# servo_controller_1_2.net
KiCad netlist of a schematic drawn in EAGLE
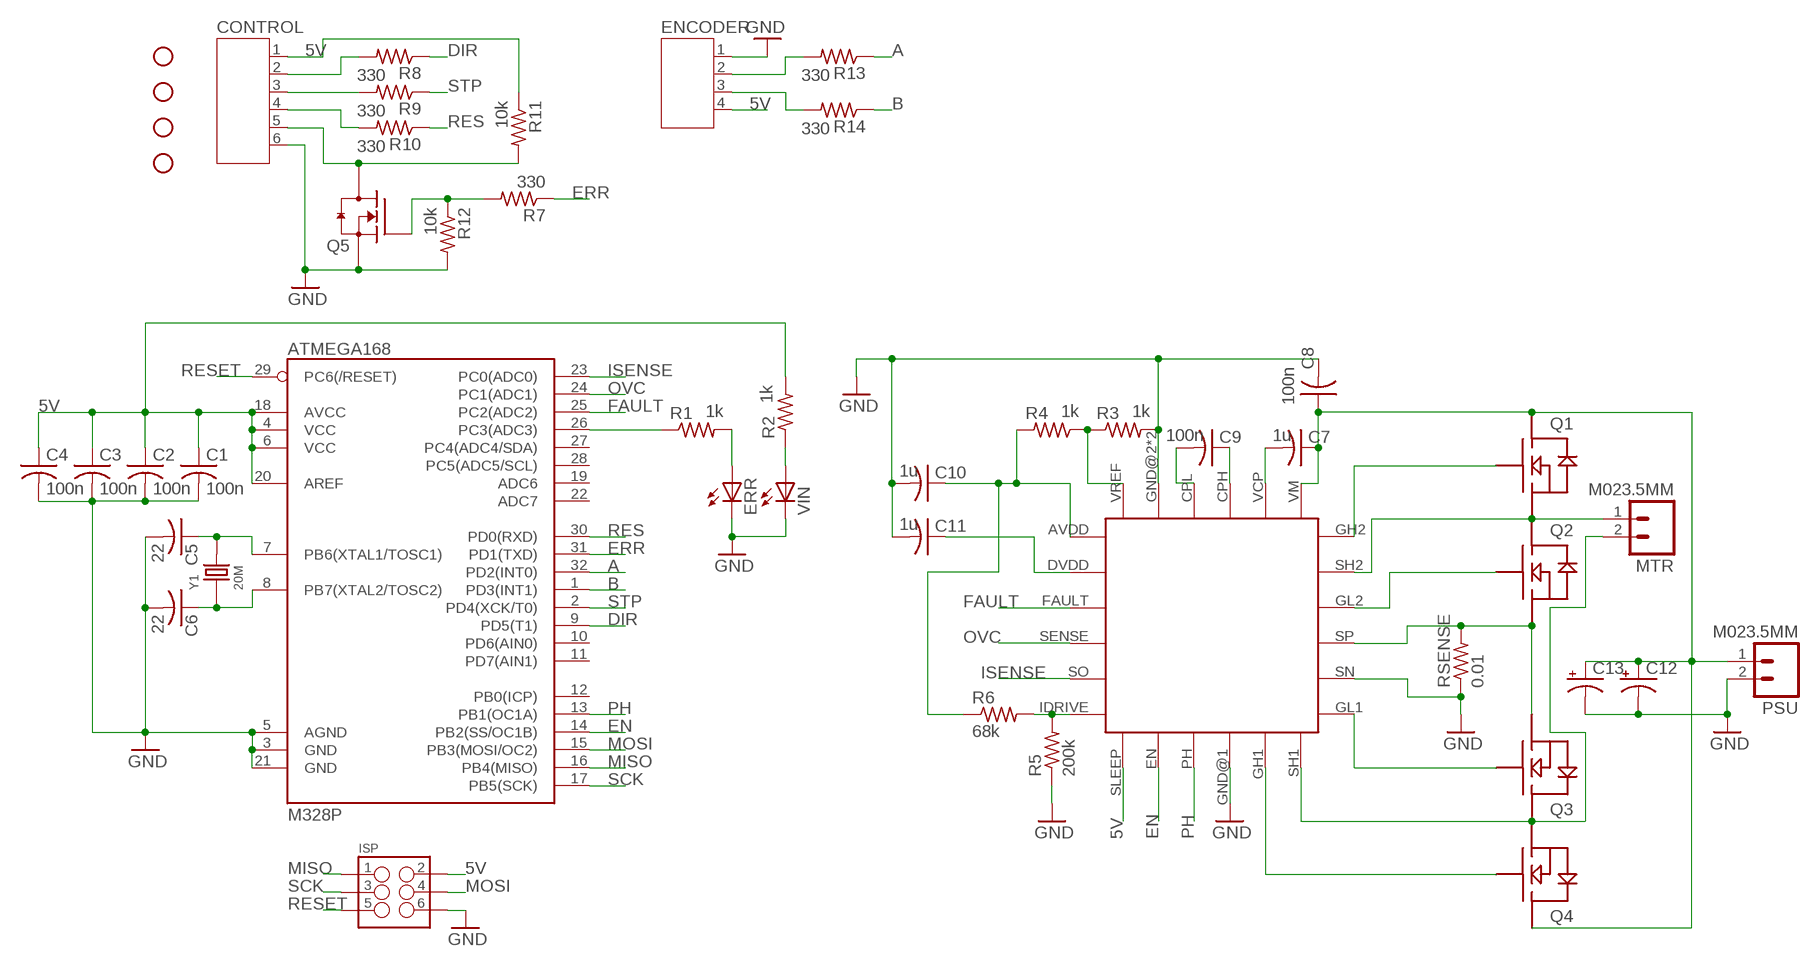
[diagram p0: schematic, sheet 1]

(export (version "E")
  (design (tool "Eeschema 10.0.6"))
  (components
    (comp (ref "8701")
      (value "DRV8701")
      (footprint "eagle-import:VQFN24")
      (libsource (lib "eagle-import") (part "DRV8701"))
    )
    (comp (ref "C1")
      (value "100n")
      (footprint "eagle-import:C0603")
      (libsource (lib "eagle-import") (part "C-USC0603"))
    )
    (comp (ref "C2")
      (value "100n")
      (footprint "eagle-import:C0603")
      (libsource (lib "eagle-import") (part "C-USC0603"))
    )
    (comp (ref "C3")
      (value "100n")
      (footprint "eagle-import:C0603")
      (libsource (lib "eagle-import") (part "C-USC0603"))
    )
    (comp (ref "C4")
      (value "100n")
      (footprint "eagle-import:C0603")
      (libsource (lib "eagle-import") (part "C-USC0603"))
    )
    (comp (ref "C5")
      (value "22")
      (footprint "eagle-import:C0603")
      (libsource (lib "eagle-import") (part "C-USC0603"))
    )
    (comp (ref "C6")
      (value "22")
      (footprint "eagle-import:C0603")
      (libsource (lib "eagle-import") (part "C-USC0603"))
    )
    (comp (ref "C7")
      (value "1u")
      (footprint "eagle-import:C0603")
      (libsource (lib "eagle-import") (part "C-USC0603"))
    )
    (comp (ref "C8")
      (value "100n")
      (footprint "eagle-import:C0603")
      (libsource (lib "eagle-import") (part "C-USC0603"))
    )
    (comp (ref "C9")
      (value "100n")
      (footprint "eagle-import:C0603")
      (libsource (lib "eagle-import") (part "C-USC0603"))
    )
    (comp (ref "C10")
      (value "1u")
      (footprint "eagle-import:C0603")
      (libsource (lib "eagle-import") (part "C-USC0603"))
    )
    (comp (ref "C11")
      (value "1u")
      (footprint "eagle-import:C0603")
      (libsource (lib "eagle-import") (part "C-USC0603"))
    )
    (comp (ref "C12")
      (value "CPOL-USE5-8.5")
      (footprint "eagle-import:E5-8,5")
      (libsource (lib "eagle-import") (part "CPOL-USE5-8.5"))
    )
    (comp (ref "C13")
      (value "CPOL-USE5-8.5")
      (footprint "eagle-import:E5-8,5")
      (libsource (lib "eagle-import") (part "CPOL-USE5-8.5"))
    )
    (comp (ref "CONTROL")
      (value "JST-PH6")
      (footprint "eagle-import:JST-PH6")
      (libsource (lib "eagle-import") (part "JST-PH6"))
    )
    (comp (ref "ENCODER")
      (value "JST-PH4")
      (footprint "eagle-import:JST-PH4")
      (libsource (lib "eagle-import") (part "JST-PH4"))
    )
    (comp (ref "ERR")
      (value "LEDCHIP-LED0603")
      (footprint "eagle-import:CHIP-LED0603")
      (libsource (lib "eagle-import") (part "LEDCHIP-LED0603"))
    )
    (comp (ref "ISP")
      (value "M03X22X3_SILK_SM")
      (footprint "eagle-import:2X3")
      (libsource (lib "eagle-import") (part "M03X22X3_SILK_SM"))
    )
    (comp (ref "M328P")
      (value "ATMEGA168")
      (footprint "eagle-import:TQFP32-08")
      (libsource (lib "eagle-import") (part "ATMEGA168"))
    )
    (comp (ref "MTR")
      (value "M023.5MM")
      (footprint "eagle-import:SCREWTERMINAL-3.5MM-2")
      (libsource (lib "eagle-import") (part "M023.5MM"))
    )
    (comp (ref "PSU")
      (value "M023.5MM")
      (footprint "eagle-import:SCREWTERMINAL-3.5MM-2")
      (libsource (lib "eagle-import") (part "M023.5MM"))
    )
    (comp (ref "Q1")
      (value "NEXFET_SINGLECSD18537NQ5A")
      (footprint "eagle-import:SON5X6")
      (libsource (lib "eagle-import") (part "NEXFET_SINGLECSD18537NQ5A"))
    )
    (comp (ref "Q2")
      (value "NEXFET_SINGLECSD18537NQ5A")
      (footprint "eagle-import:SON5X6")
      (libsource (lib "eagle-import") (part "NEXFET_SINGLECSD18537NQ5A"))
    )
    (comp (ref "Q3")
      (value "NEXFET_SINGLECSD18537NQ5A")
      (footprint "eagle-import:SON5X6")
      (libsource (lib "eagle-import") (part "NEXFET_SINGLECSD18537NQ5A"))
    )
    (comp (ref "Q4")
      (value "NEXFET_SINGLECSD18537NQ5A")
      (footprint "eagle-import:SON5X6")
      (libsource (lib "eagle-import") (part "NEXFET_SINGLECSD18537NQ5A"))
    )
    (comp (ref "Q5")
      (value "MOSFET-NCH_SOT-23")
      (footprint "eagle-import:SOT95P280X135-3N")
      (libsource (lib "eagle-import") (part "MOSFET-NCH_SOT-23"))
    )
    (comp (ref "R1")
      (value "1k")
      (footprint "eagle-import:R0603")
      (libsource (lib "eagle-import") (part "R-US_R0603"))
    )
    (comp (ref "R2")
      (value "1k")
      (footprint "eagle-import:R0603")
      (libsource (lib "eagle-import") (part "R-US_R0603"))
    )
    (comp (ref "R3")
      (value "1k")
      (footprint "eagle-import:R0603")
      (libsource (lib "eagle-import") (part "R-US_R0603"))
    )
    (comp (ref "R4")
      (value "1k")
      (footprint "eagle-import:R0603")
      (libsource (lib "eagle-import") (part "R-US_R0603"))
    )
    (comp (ref "R5")
      (value "200k")
      (footprint "eagle-import:R0603")
      (libsource (lib "eagle-import") (part "R-US_R0603"))
    )
    (comp (ref "R6")
      (value "68k")
      (footprint "eagle-import:R0603")
      (libsource (lib "eagle-import") (part "R-US_R0603"))
    )
    (comp (ref "R7")
      (value "330")
      (footprint "eagle-import:R0603")
      (libsource (lib "eagle-import") (part "R-US_R0603"))
    )
    (comp (ref "R8")
      (value "330")
      (footprint "eagle-import:R0603")
      (libsource (lib "eagle-import") (part "R-US_R0603"))
    )
    (comp (ref "R9")
      (value "330")
      (footprint "eagle-import:R0603")
      (libsource (lib "eagle-import") (part "R-US_R0603"))
    )
    (comp (ref "R10")
      (value "330")
      (footprint "eagle-import:R0603")
      (libsource (lib "eagle-import") (part "R-US_R0603"))
    )
    (comp (ref "R11")
      (value "10k")
      (footprint "eagle-import:R0603")
      (libsource (lib "eagle-import") (part "R-US_R0603"))
    )
    (comp (ref "R12")
      (value "10k")
      (footprint "eagle-import:R0603")
      (libsource (lib "eagle-import") (part "R-US_R0603"))
    )
    (comp (ref "R13")
      (value "330")
      (footprint "eagle-import:R0603")
      (libsource (lib "eagle-import") (part "R-US_R0603"))
    )
    (comp (ref "R14")
      (value "330")
      (footprint "eagle-import:R0603")
      (libsource (lib "eagle-import") (part "R-US_R0603"))
    )
    (comp (ref "RSENSE")
      (value "0.01")
      (footprint "eagle-import:R2512")
      (libsource (lib "eagle-import") (part "R-US_R2512"))
    )
    (comp (ref "STANDOFF1")
      (value "STAND-OFF")
      (footprint "eagle-import:STAND-OFF")
      (libsource (lib "eagle-import") (part "STAND-OFF"))
    )
    (comp (ref "STANDOFF2")
      (value "STAND-OFF")
      (footprint "eagle-import:STAND-OFF")
      (libsource (lib "eagle-import") (part "STAND-OFF"))
    )
    (comp (ref "STANDOFF3")
      (value "STAND-OFF")
      (footprint "eagle-import:STAND-OFF")
      (libsource (lib "eagle-import") (part "STAND-OFF"))
    )
    (comp (ref "STANDOFF4")
      (value "STAND-OFF")
      (footprint "eagle-import:STAND-OFF")
      (libsource (lib "eagle-import") (part "STAND-OFF"))
    )
    (comp (ref "VIN")
      (value "LEDCHIP-LED0603")
      (footprint "eagle-import:CHIP-LED0603")
      (libsource (lib "eagle-import") (part "LEDCHIP-LED0603"))
    )
    (comp (ref "Y1")
      (value "20M")
      (footprint "eagle-import:X2-SMD-5.0X3.2X1.3MM")
      (fields (field (name "MPN") "X053201602002"))
      (libsource (lib "eagle-import") (part "SMD-CRYSTAL-16MHZ-8PF-20PPM-40R(2P-5.0X3.2MM)"))
    )
  )
  (nets
    (net (code "1") (name "/5V") (class "Default")
      (node (ref "8701") (pin "SLEEP") (pinfunction "SLEEP_SLEEP") (pintype "bidirectional"))
      (node (ref "C1") (pin "1") (pinfunction "1_1") (pintype "passive"))
      (node (ref "C2") (pin "1") (pinfunction "1_1") (pintype "passive"))
      (node (ref "C3") (pin "1") (pinfunction "1_1") (pintype "passive"))
      (node (ref "C4") (pin "1") (pinfunction "1_1") (pintype "passive"))
      (node (ref "CONTROL") (pin "1") (pinfunction "1_1") (pintype "passive"))
      (node (ref "ENCODER") (pin "4") (pinfunction "4_4") (pintype "passive"))
      (node (ref "ISP") (pin "2") (pinfunction "2_2") (pintype "bidirectional"))
      (node (ref "M328P") (pin "18") (pinfunction "AVCC_18") (pintype "bidirectional"))
      (node (ref "M328P") (pin "20") (pinfunction "AREF_20") (pintype "bidirectional"))
      (node (ref "M328P") (pin "4") (pinfunction "VCC_4") (pintype "bidirectional"))
      (node (ref "M328P") (pin "6") (pinfunction "VCC_6") (pintype "bidirectional"))
      (node (ref "R11") (pin "1") (pinfunction "1_1") (pintype "passive"))
      (node (ref "R2") (pin "2") (pinfunction "2_2") (pintype "passive"))
    )
    (net (code "2") (name "/A") (class "Default")
      (node (ref "M328P") (pin "32") (pinfunction "PD2(INT0)_32") (pintype "bidirectional"))
      (node (ref "R13") (pin "1") (pinfunction "1_1") (pintype "passive"))
    )
    (net (code "3") (name "/B") (class "Default")
      (node (ref "M328P") (pin "1") (pinfunction "PD3(INT1)_1") (pintype "bidirectional"))
      (node (ref "R14") (pin "1") (pinfunction "1_1") (pintype "passive"))
    )
    (net (code "4") (name "/DIR") (class "Default")
      (node (ref "M328P") (pin "9") (pinfunction "PD5(T1)_9") (pintype "bidirectional"))
      (node (ref "R8") (pin "1") (pinfunction "1_1") (pintype "passive"))
    )
    (net (code "5") (name "/EN") (class "Default")
      (node (ref "8701") (pin "EN") (pinfunction "EN_EN") (pintype "bidirectional"))
      (node (ref "M328P") (pin "14") (pinfunction "PB2(SS/OC1B)_14") (pintype "bidirectional"))
    )
    (net (code "6") (name "/ERR") (class "Default")
      (node (ref "M328P") (pin "31") (pinfunction "PD1(TXD)_31") (pintype "bidirectional"))
      (node (ref "R7") (pin "1") (pinfunction "1_1") (pintype "passive"))
    )
    (net (code "7") (name "/FAULT") (class "Default")
      (node (ref "8701") (pin "FAULT") (pinfunction "FAULT_FAULT") (pintype "bidirectional"))
      (node (ref "M328P") (pin "25") (pinfunction "PC2(ADC2)_25") (pintype "bidirectional"))
    )
    (net (code "8") (name "/ISENSE") (class "Default")
      (node (ref "8701") (pin "SO") (pinfunction "SO_SO") (pintype "bidirectional"))
      (node (ref "M328P") (pin "23") (pinfunction "PC0(ADC0)_23") (pintype "bidirectional"))
    )
    (net (code "9") (name "/MISO") (class "Default")
      (node (ref "ISP") (pin "1") (pinfunction "1_1") (pintype "bidirectional"))
      (node (ref "M328P") (pin "16") (pinfunction "PB4(MISO)_16") (pintype "bidirectional"))
    )
    (net (code "10") (name "/MOSI") (class "Default")
      (node (ref "ISP") (pin "4") (pinfunction "4_4") (pintype "bidirectional"))
      (node (ref "M328P") (pin "15") (pinfunction "PB3(MOSI/OC2)_15") (pintype "bidirectional"))
    )
    (net (code "11") (name "/OVC") (class "Default")
      (node (ref "8701") (pin "SENSE") (pinfunction "SENSE_SENSE") (pintype "bidirectional"))
      (node (ref "M328P") (pin "24") (pinfunction "PC1(ADC1)_24") (pintype "bidirectional"))
    )
    (net (code "12") (name "/PH") (class "Default")
      (node (ref "8701") (pin "PH") (pinfunction "PH_PH") (pintype "bidirectional"))
      (node (ref "M328P") (pin "13") (pinfunction "PB1(OC1A)_13") (pintype "bidirectional"))
    )
    (net (code "13") (name "/RES") (class "Default")
      (node (ref "M328P") (pin "30") (pinfunction "PD0(RXD)_30") (pintype "bidirectional"))
      (node (ref "R10") (pin "1") (pinfunction "1_1") (pintype "passive"))
    )
    (net (code "14") (name "/RESET") (class "Default")
      (node (ref "ISP") (pin "5") (pinfunction "5_5") (pintype "bidirectional"))
      (node (ref "M328P") (pin "29") (pinfunction "PC6(/RESET)_29") (pintype "bidirectional"))
    )
    (net (code "15") (name "/SCK") (class "Default")
      (node (ref "ISP") (pin "3") (pinfunction "3_3") (pintype "bidirectional"))
      (node (ref "M328P") (pin "17") (pinfunction "PB5(SCK)_17") (pintype "bidirectional"))
    )
    (net (code "16") (name "/STP") (class "Default")
      (node (ref "M328P") (pin "2") (pinfunction "PD4(XCK/T0)_2") (pintype "bidirectional"))
      (node (ref "R9") (pin "1") (pinfunction "1_1") (pintype "passive"))
    )
    (net (code "17") (name "GND") (class "Default")
      (node (ref "8701") (pin "GND@1") (pinfunction "GND_GND@1") (pintype "bidirectional"))
      (node (ref "8701") (pin "GND@2") (pinfunction "GND_GND@2") (pintype "bidirectional"))
      (node (ref "8701") (pin "GND@3") (pinfunction "GND_GND@3") (pintype "bidirectional"))
      (node (ref "8701") (pin "SN") (pinfunction "SN_SN") (pintype "bidirectional"))
      (node (ref "C1") (pin "2") (pinfunction "2_2") (pintype "passive"))
      (node (ref "C10") (pin "2") (pinfunction "2_2") (pintype "passive"))
      (node (ref "C11") (pin "2") (pinfunction "2_2") (pintype "passive"))
      (node (ref "C12") (pin "-") (pinfunction "-_-") (pintype "passive"))
      (node (ref "C13") (pin "-") (pinfunction "-_-") (pintype "passive"))
      (node (ref "C2") (pin "2") (pinfunction "2_2") (pintype "passive"))
      (node (ref "C3") (pin "2") (pinfunction "2_2") (pintype "passive"))
      (node (ref "C4") (pin "2") (pinfunction "2_2") (pintype "passive"))
      (node (ref "C5") (pin "2") (pinfunction "2_2") (pintype "passive"))
      (node (ref "C6") (pin "2") (pinfunction "2_2") (pintype "passive"))
      (node (ref "C8") (pin "2") (pinfunction "2_2") (pintype "passive"))
      (node (ref "CONTROL") (pin "6") (pinfunction "6_6") (pintype "passive"))
      (node (ref "ENCODER") (pin "1") (pinfunction "1_1") (pintype "passive"))
      (node (ref "ERR") (pin "C") (pinfunction "C_C") (pintype "passive"))
      (node (ref "ISP") (pin "6") (pinfunction "6_6") (pintype "bidirectional"))
      (node (ref "M328P") (pin "21") (pinfunction "GND_21") (pintype "bidirectional"))
      (node (ref "M328P") (pin "3") (pinfunction "GND_3") (pintype "bidirectional"))
      (node (ref "M328P") (pin "5") (pinfunction "AGND_5") (pintype "bidirectional"))
      (node (ref "PSU") (pin "2") (pinfunction "2_2") (pintype "passive"))
      (node (ref "Q5") (pin "2") (pinfunction "S_2") (pintype "passive"))
      (node (ref "R12") (pin "2") (pinfunction "2_2") (pintype "passive"))
      (node (ref "R3") (pin "2") (pinfunction "2_2") (pintype "passive"))
      (node (ref "R5") (pin "1") (pinfunction "1_1") (pintype "passive"))
      (node (ref "RSENSE") (pin "1") (pinfunction "1_1") (pintype "passive"))
      (node (ref "VIN") (pin "C") (pinfunction "C_C") (pintype "passive"))
    )
    (net (code "18") (name "Net-(8701-PadAVDD)") (class "Default")
      (node (ref "8701") (pin "AVDD") (pinfunction "AVDD_AVDD") (pintype "bidirectional"))
      (node (ref "C10") (pin "1") (pinfunction "1_1") (pintype "passive"))
      (node (ref "R4") (pin "2") (pinfunction "2_2") (pintype "passive"))
      (node (ref "R6") (pin "1") (pinfunction "1_1") (pintype "passive"))
    )
    (net (code "19") (name "Net-(8701-PadCPH)") (class "Default")
      (node (ref "8701") (pin "CPH") (pinfunction "CPH_CPH") (pintype "bidirectional"))
      (node (ref "C9") (pin "1") (pinfunction "1_1") (pintype "passive"))
    )
    (net (code "20") (name "Net-(8701-PadCPL)") (class "Default")
      (node (ref "8701") (pin "CPL") (pinfunction "CPL_CPL") (pintype "bidirectional"))
      (node (ref "C9") (pin "2") (pinfunction "2_2") (pintype "passive"))
    )
    (net (code "21") (name "Net-(8701-PadDVDD)") (class "Default")
      (node (ref "8701") (pin "DVDD") (pinfunction "DVDD_DVDD") (pintype "bidirectional"))
      (node (ref "C11") (pin "1") (pinfunction "1_1") (pintype "passive"))
    )
    (net (code "22") (name "Net-(8701-PadGH1)") (class "Default")
      (node (ref "8701") (pin "GH1") (pinfunction "GH1_GH1") (pintype "bidirectional"))
      (node (ref "Q4") (pin "GATE") (pinfunction "GATE_GATE") (pintype "bidirectional"))
    )
    (net (code "23") (name "Net-(8701-PadGH2)") (class "Default")
      (node (ref "8701") (pin "GH2") (pinfunction "GH2_GH2") (pintype "bidirectional"))
      (node (ref "Q1") (pin "GATE") (pinfunction "GATE_GATE") (pintype "bidirectional"))
    )
    (net (code "24") (name "Net-(8701-PadGL1)") (class "Default")
      (node (ref "8701") (pin "GL1") (pinfunction "GL1_GL1") (pintype "bidirectional"))
      (node (ref "Q3") (pin "GATE") (pinfunction "GATE_GATE") (pintype "bidirectional"))
    )
    (net (code "25") (name "Net-(8701-PadGL2)") (class "Default")
      (node (ref "8701") (pin "GL2") (pinfunction "GL2_GL2") (pintype "bidirectional"))
      (node (ref "Q2") (pin "GATE") (pinfunction "GATE_GATE") (pintype "bidirectional"))
    )
    (net (code "26") (name "Net-(8701-PadIDRIVE)") (class "Default")
      (node (ref "8701") (pin "IDRIVE") (pinfunction "IDRIVE_IDRIVE") (pintype "bidirectional"))
      (node (ref "R5") (pin "2") (pinfunction "2_2") (pintype "passive"))
      (node (ref "R6") (pin "2") (pinfunction "2_2") (pintype "passive"))
    )
    (net (code "27") (name "Net-(8701-PadSH1)") (class "Default")
      (node (ref "8701") (pin "SH1") (pinfunction "SH1_SH1") (pintype "bidirectional"))
      (node (ref "MTR") (pin "2") (pinfunction "2_2") (pintype "passive"))
      (node (ref "Q3") (pin "DRAIN@1") (pinfunction "DRAIN_DRAIN@1") (pintype "bidirectional"))
      (node (ref "Q3") (pin "DRAIN@2") (pinfunction "DRAIN_DRAIN@2") (pintype "bidirectional"))
      (node (ref "Q3") (pin "DRAIN@3") (pinfunction "DRAIN_DRAIN@3") (pintype "bidirectional"))
      (node (ref "Q3") (pin "DRAIN@4") (pinfunction "DRAIN_DRAIN@4") (pintype "bidirectional"))
      (node (ref "Q3") (pin "DRAIN@5") (pinfunction "DRAIN_DRAIN@5") (pintype "bidirectional"))
      (node (ref "Q4") (pin "SOURCE@1") (pinfunction "SOURCE_SOURCE@1") (pintype "bidirectional"))
      (node (ref "Q4") (pin "SOURCE@2") (pinfunction "SOURCE_SOURCE@2") (pintype "bidirectional"))
      (node (ref "Q4") (pin "SOURCE@3") (pinfunction "SOURCE_SOURCE@3") (pintype "bidirectional"))
    )
    (net (code "28") (name "Net-(8701-PadSH2)") (class "Default")
      (node (ref "8701") (pin "SH2") (pinfunction "SH2_SH2") (pintype "bidirectional"))
      (node (ref "MTR") (pin "1") (pinfunction "1_1") (pintype "passive"))
      (node (ref "Q1") (pin "SOURCE@1") (pinfunction "SOURCE_SOURCE@1") (pintype "bidirectional"))
      (node (ref "Q1") (pin "SOURCE@2") (pinfunction "SOURCE_SOURCE@2") (pintype "bidirectional"))
      (node (ref "Q1") (pin "SOURCE@3") (pinfunction "SOURCE_SOURCE@3") (pintype "bidirectional"))
      (node (ref "Q2") (pin "DRAIN@1") (pinfunction "DRAIN_DRAIN@1") (pintype "bidirectional"))
      (node (ref "Q2") (pin "DRAIN@2") (pinfunction "DRAIN_DRAIN@2") (pintype "bidirectional"))
      (node (ref "Q2") (pin "DRAIN@3") (pinfunction "DRAIN_DRAIN@3") (pintype "bidirectional"))
      (node (ref "Q2") (pin "DRAIN@4") (pinfunction "DRAIN_DRAIN@4") (pintype "bidirectional"))
      (node (ref "Q2") (pin "DRAIN@5") (pinfunction "DRAIN_DRAIN@5") (pintype "bidirectional"))
    )
    (net (code "29") (name "Net-(8701-PadSP)") (class "Default")
      (node (ref "8701") (pin "SP") (pinfunction "SP_SP") (pintype "bidirectional"))
      (node (ref "Q2") (pin "SOURCE@1") (pinfunction "SOURCE_SOURCE@1") (pintype "bidirectional"))
      (node (ref "Q2") (pin "SOURCE@2") (pinfunction "SOURCE_SOURCE@2") (pintype "bidirectional"))
      (node (ref "Q2") (pin "SOURCE@3") (pinfunction "SOURCE_SOURCE@3") (pintype "bidirectional"))
      (node (ref "Q3") (pin "SOURCE@1") (pinfunction "SOURCE_SOURCE@1") (pintype "bidirectional"))
      (node (ref "Q3") (pin "SOURCE@2") (pinfunction "SOURCE_SOURCE@2") (pintype "bidirectional"))
      (node (ref "Q3") (pin "SOURCE@3") (pinfunction "SOURCE_SOURCE@3") (pintype "bidirectional"))
      (node (ref "RSENSE") (pin "2") (pinfunction "2_2") (pintype "passive"))
    )
    (net (code "30") (name "Net-(8701-PadVCP)") (class "Default")
      (node (ref "8701") (pin "VCP") (pinfunction "VCP_VCP") (pintype "bidirectional"))
      (node (ref "C7") (pin "2") (pinfunction "2_2") (pintype "passive"))
    )
    (net (code "31") (name "Net-(8701-PadVM)") (class "Default")
      (node (ref "8701") (pin "VM") (pinfunction "VM_VM") (pintype "bidirectional"))
      (node (ref "C12") (pin "+") (pinfunction "+_+") (pintype "passive"))
      (node (ref "C13") (pin "+") (pinfunction "+_+") (pintype "passive"))
      (node (ref "C7") (pin "1") (pinfunction "1_1") (pintype "passive"))
      (node (ref "C8") (pin "1") (pinfunction "1_1") (pintype "passive"))
      (node (ref "PSU") (pin "1") (pinfunction "1_1") (pintype "passive"))
      (node (ref "Q1") (pin "DRAIN@1") (pinfunction "DRAIN_DRAIN@1") (pintype "bidirectional"))
      (node (ref "Q1") (pin "DRAIN@2") (pinfunction "DRAIN_DRAIN@2") (pintype "bidirectional"))
      (node (ref "Q1") (pin "DRAIN@3") (pinfunction "DRAIN_DRAIN@3") (pintype "bidirectional"))
      (node (ref "Q1") (pin "DRAIN@4") (pinfunction "DRAIN_DRAIN@4") (pintype "bidirectional"))
      (node (ref "Q1") (pin "DRAIN@5") (pinfunction "DRAIN_DRAIN@5") (pintype "bidirectional"))
      (node (ref "Q4") (pin "DRAIN@1") (pinfunction "DRAIN_DRAIN@1") (pintype "bidirectional"))
      (node (ref "Q4") (pin "DRAIN@2") (pinfunction "DRAIN_DRAIN@2") (pintype "bidirectional"))
      (node (ref "Q4") (pin "DRAIN@3") (pinfunction "DRAIN_DRAIN@3") (pintype "bidirectional"))
      (node (ref "Q4") (pin "DRAIN@4") (pinfunction "DRAIN_DRAIN@4") (pintype "bidirectional"))
      (node (ref "Q4") (pin "DRAIN@5") (pinfunction "DRAIN_DRAIN@5") (pintype "bidirectional"))
    )
    (net (code "32") (name "Net-(8701-PadVREF)") (class "Default")
      (node (ref "8701") (pin "VREF") (pinfunction "VREF_VREF") (pintype "bidirectional"))
      (node (ref "R3") (pin "1") (pinfunction "1_1") (pintype "passive"))
      (node (ref "R4") (pin "1") (pinfunction "1_1") (pintype "passive"))
    )
    (net (code "33") (name "Net-(CONTROL-Pad2)") (class "Default")
      (node (ref "CONTROL") (pin "2") (pinfunction "2_2") (pintype "passive"))
      (node (ref "R8") (pin "2") (pinfunction "2_2") (pintype "passive"))
    )
    (net (code "34") (name "Net-(CONTROL-Pad3)") (class "Default")
      (node (ref "CONTROL") (pin "3") (pinfunction "3_3") (pintype "passive"))
      (node (ref "R9") (pin "2") (pinfunction "2_2") (pintype "passive"))
    )
    (net (code "35") (name "Net-(CONTROL-Pad4)") (class "Default")
      (node (ref "CONTROL") (pin "4") (pinfunction "4_4") (pintype "passive"))
      (node (ref "R10") (pin "2") (pinfunction "2_2") (pintype "passive"))
    )
    (net (code "36") (name "Net-(ENCODER-Pad2)") (class "Default")
      (node (ref "ENCODER") (pin "2") (pinfunction "2_2") (pintype "passive"))
      (node (ref "R13") (pin "2") (pinfunction "2_2") (pintype "passive"))
    )
    (net (code "37") (name "Net-(ENCODER-Pad3)") (class "Default")
      (node (ref "ENCODER") (pin "3") (pinfunction "3_3") (pintype "passive"))
      (node (ref "R14") (pin "2") (pinfunction "2_2") (pintype "passive"))
    )
    (net (code "38") (name "Net-(ERR-PadA)") (class "Default")
      (node (ref "ERR") (pin "A") (pinfunction "A_A") (pintype "passive"))
      (node (ref "R1") (pin "2") (pinfunction "2_2") (pintype "passive"))
    )
    (net (code "39") (name "Net-(M328P-PB6(XTAL1{slash}TOSC1))") (class "Default")
      (node (ref "C5") (pin "1") (pinfunction "1_1") (pintype "passive"))
      (node (ref "M328P") (pin "7") (pinfunction "PB6(XTAL1/TOSC1)_7") (pintype "bidirectional"))
      (node (ref "Y1") (pin "2") (pinfunction "2_2") (pintype "passive"))
    )
    (net (code "40") (name "Net-(M328P-PB7(XTAL2{slash}TOSC2))") (class "Default")
      (node (ref "C6") (pin "1") (pinfunction "1_1") (pintype "passive"))
      (node (ref "M328P") (pin "8") (pinfunction "PB7(XTAL2/TOSC2)_8") (pintype "bidirectional"))
      (node (ref "Y1") (pin "1") (pinfunction "1_1") (pintype "passive"))
    )
    (net (code "41") (name "Net-(M328P-PC3(ADC3))") (class "Default")
      (node (ref "M328P") (pin "26") (pinfunction "PC3(ADC3)_26") (pintype "bidirectional"))
      (node (ref "R1") (pin "1") (pinfunction "1_1") (pintype "passive"))
    )
    (net (code "42") (name "Net-(Q5-D)") (class "Default")
      (node (ref "CONTROL") (pin "5") (pinfunction "5_5") (pintype "passive"))
      (node (ref "Q5") (pin "3") (pinfunction "D_3") (pintype "passive"))
      (node (ref "R11") (pin "2") (pinfunction "2_2") (pintype "passive"))
    )
    (net (code "43") (name "Net-(Q5-G)") (class "Default")
      (node (ref "Q5") (pin "1") (pinfunction "G_1") (pintype "passive"))
      (node (ref "R12") (pin "1") (pinfunction "1_1") (pintype "passive"))
      (node (ref "R7") (pin "2") (pinfunction "2_2") (pintype "passive"))
    )
    (net (code "44") (name "Net-(R2-Pad1)") (class "Default")
      (node (ref "R2") (pin "1") (pinfunction "1_1") (pintype "passive"))
      (node (ref "VIN") (pin "A") (pinfunction "A_A") (pintype "passive"))
    )
    (net (code "45") (name "unconnected-(M328P-ADC6-Pad19)") (class "Default")
      (node (ref "M328P") (pin "19") (pinfunction "ADC6_19") (pintype "bidirectional"))
    )
    (net (code "46") (name "unconnected-(M328P-ADC7-Pad22)") (class "Default")
      (node (ref "M328P") (pin "22") (pinfunction "ADC7_22") (pintype "bidirectional"))
    )
    (net (code "47") (name "unconnected-(M328P-PB0(ICP)-Pad12)") (class "Default")
      (node (ref "M328P") (pin "12") (pinfunction "PB0(ICP)_12") (pintype "bidirectional"))
    )
    (net (code "48") (name "unconnected-(M328P-PC4(ADC4{slash}SDA)-Pad27)") (class "Default")
      (node (ref "M328P") (pin "27") (pinfunction "PC4(ADC4/SDA)_27") (pintype "bidirectional"))
    )
    (net (code "49") (name "unconnected-(M328P-PC5(ADC5{slash}SCL)-Pad28)") (class "Default")
      (node (ref "M328P") (pin "28") (pinfunction "PC5(ADC5/SCL)_28") (pintype "bidirectional"))
    )
    (net (code "50") (name "unconnected-(M328P-PD6(AIN0)-Pad10)") (class "Default")
      (node (ref "M328P") (pin "10") (pinfunction "PD6(AIN0)_10") (pintype "bidirectional"))
    )
    (net (code "51") (name "unconnected-(M328P-PD7(AIN1)-Pad11)") (class "Default")
      (node (ref "M328P") (pin "11") (pinfunction "PD7(AIN1)_11") (pintype "bidirectional"))
    )
  )
)
